# sensor_hubv3.net
KiCad netlist of a schematic drawn in EAGLE
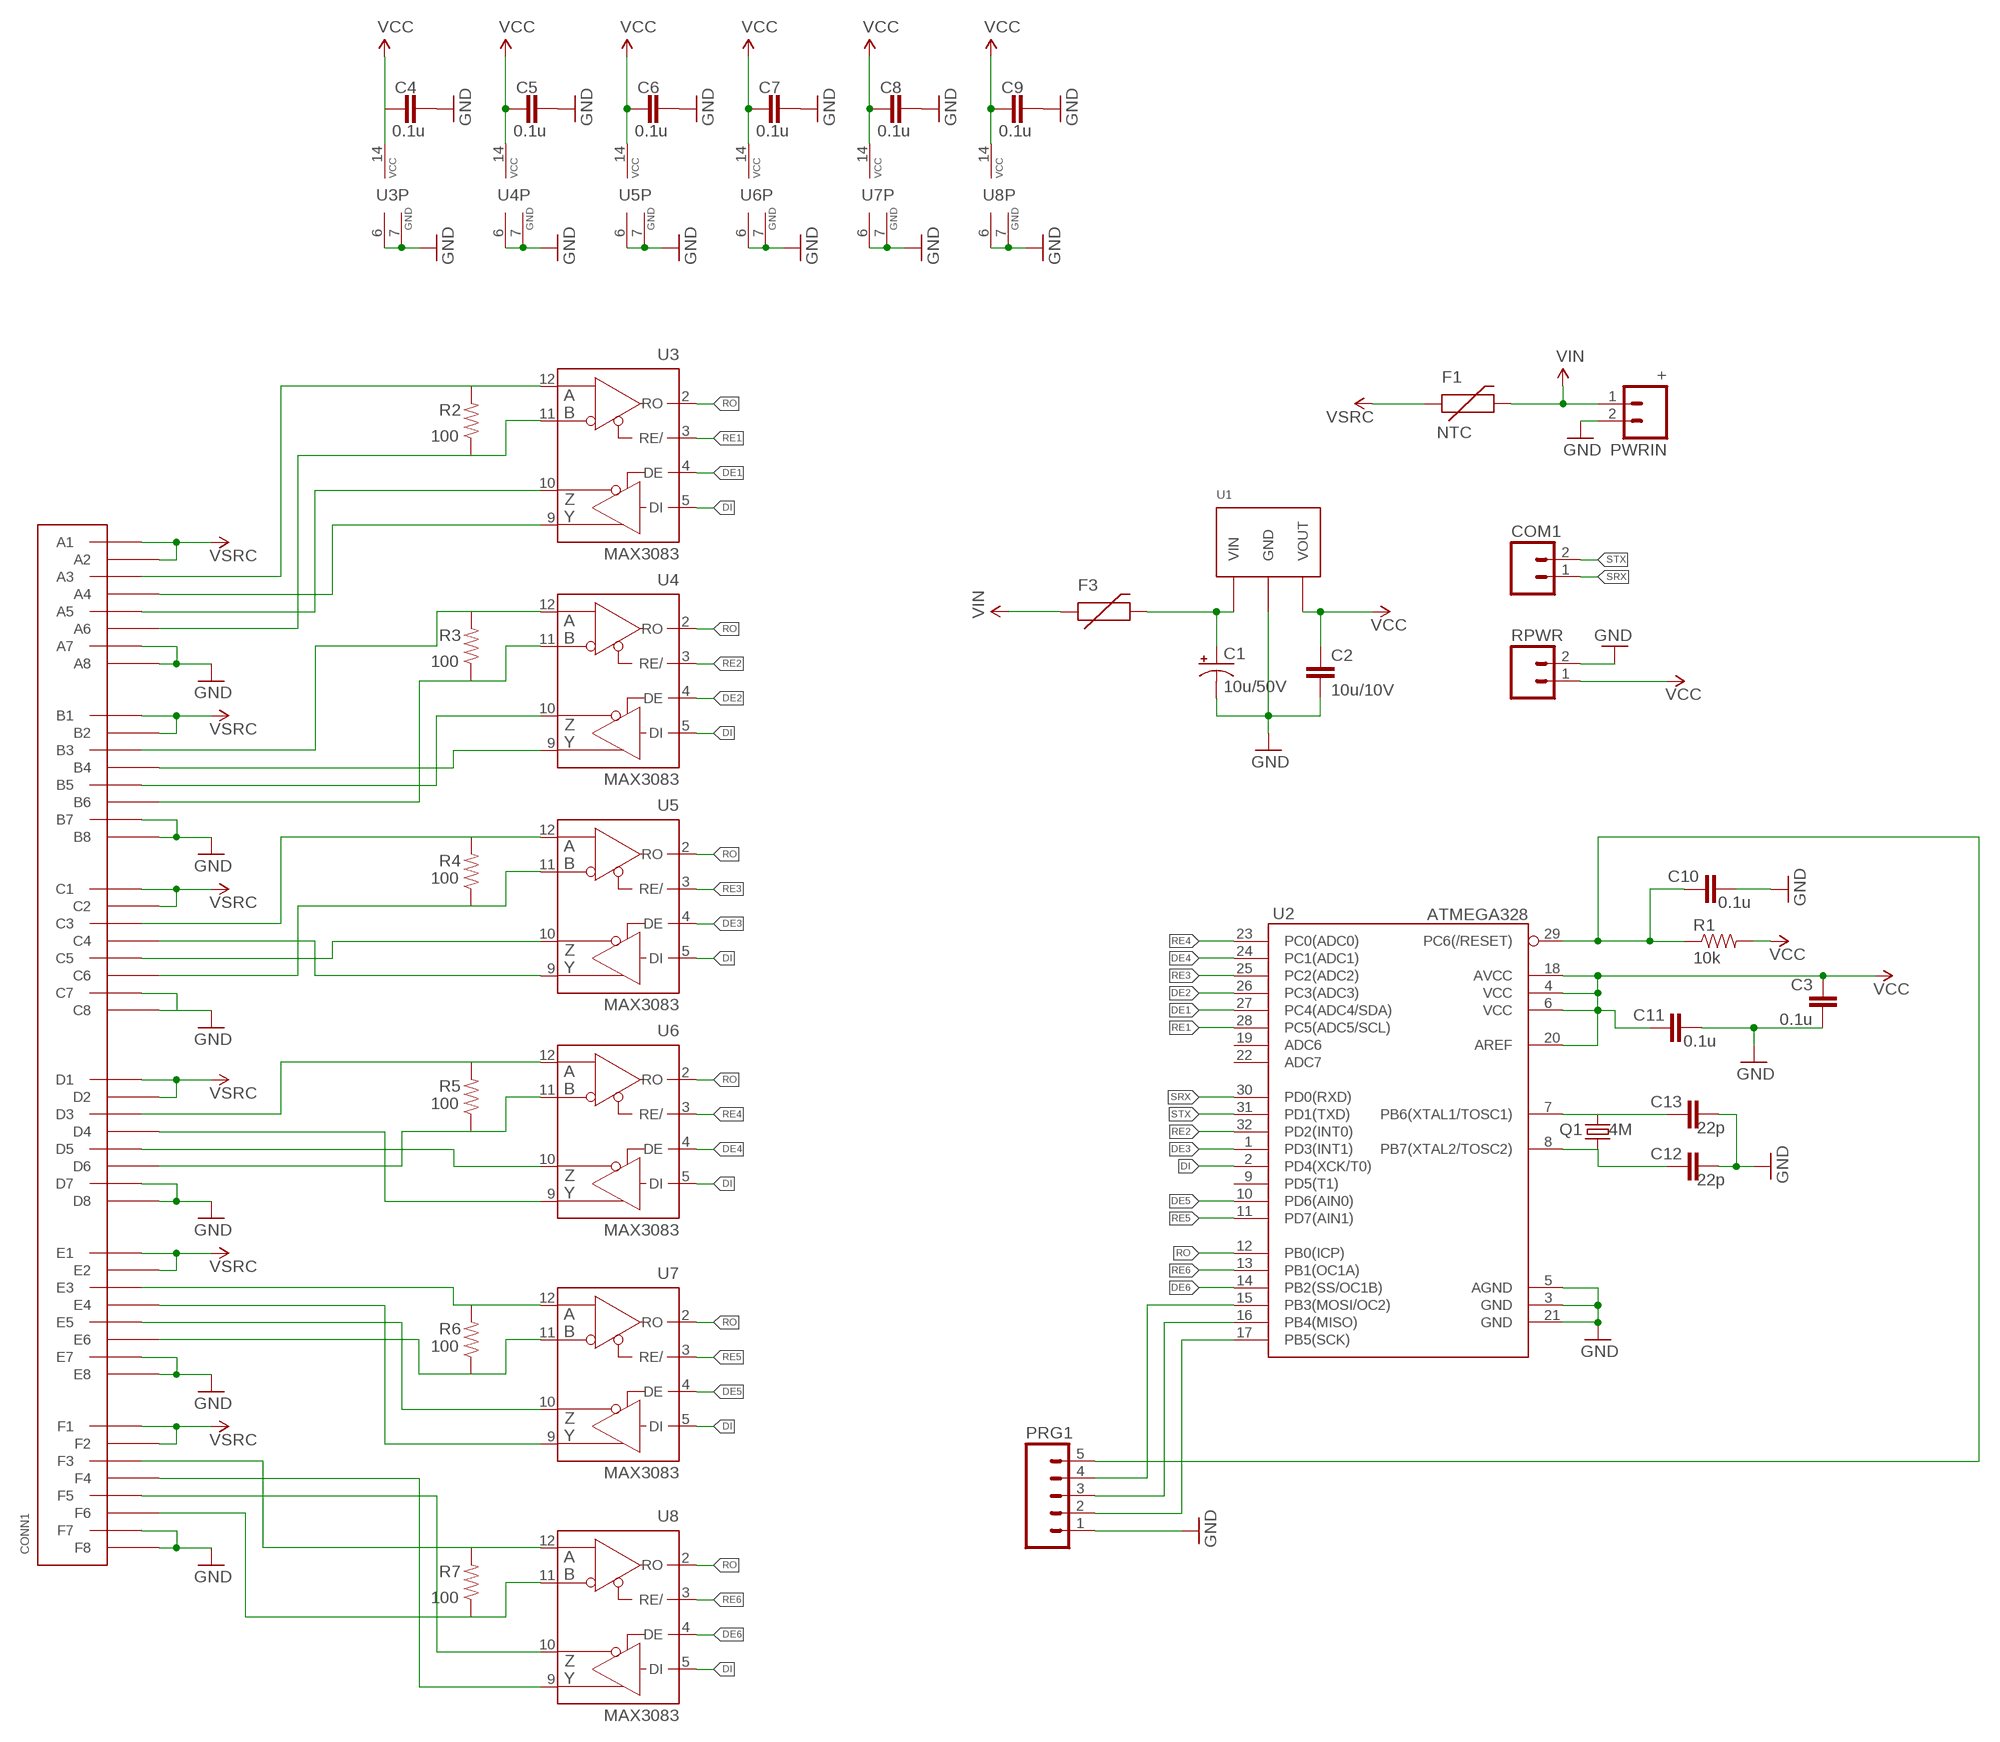
[diagram p0: schematic, sheet 1]

(export (version "E")
  (design (tool "Eeschema 10.0.6"))
  (components
    (comp (ref "C1")
      (value "10u/50V")
      (footprint "eagle-import:PANASONIC_C")
      (libsource (lib "eagle-import") (part "CAP_POLC"))
    )
    (comp (ref "C2")
      (value "10u/10V")
      (footprint "eagle-import:0805")
      (libsource (lib "eagle-import") (part "CAP0805"))
    )
    (comp (ref "C3")
      (value "0.1u")
      (footprint "eagle-import:0805")
      (libsource (lib "eagle-import") (part "CAP0805"))
    )
    (comp (ref "C4")
      (value "0.1u")
      (footprint "eagle-import:0805")
      (libsource (lib "eagle-import") (part "CAP0805"))
    )
    (comp (ref "C5")
      (value "0.1u")
      (footprint "eagle-import:0805")
      (libsource (lib "eagle-import") (part "CAP0805"))
    )
    (comp (ref "C6")
      (value "0.1u")
      (footprint "eagle-import:0805")
      (libsource (lib "eagle-import") (part "CAP0805"))
    )
    (comp (ref "C7")
      (value "0.1u")
      (footprint "eagle-import:0805")
      (libsource (lib "eagle-import") (part "CAP0805"))
    )
    (comp (ref "C8")
      (value "0.1u")
      (footprint "eagle-import:0805")
      (libsource (lib "eagle-import") (part "CAP0805"))
    )
    (comp (ref "C9")
      (value "0.1u")
      (footprint "eagle-import:0805")
      (libsource (lib "eagle-import") (part "CAP0805"))
    )
    (comp (ref "C10")
      (value "0.1u")
      (footprint "eagle-import:0805")
      (libsource (lib "eagle-import") (part "CAP0805"))
    )
    (comp (ref "C11")
      (value "0.1u")
      (footprint "eagle-import:0805")
      (libsource (lib "eagle-import") (part "CAP0805"))
    )
    (comp (ref "C12")
      (value "22p")
      (footprint "eagle-import:0805")
      (libsource (lib "eagle-import") (part "CAP0805"))
    )
    (comp (ref "C13")
      (value "22p")
      (footprint "eagle-import:0805")
      (libsource (lib "eagle-import") (part "CAP0805"))
    )
    (comp (ref "COM1")
      (value "M02LOCK_LONGPADS")
      (footprint "eagle-import:1X02_LOCK_LONGPADS")
      (libsource (lib "eagle-import") (part "M02LOCK_LONGPADS"))
    )
    (comp (ref "CONN1")
      (value "8P8C-6PORT")
      (footprint "eagle-import:4UCON-04953")
      (libsource (lib "eagle-import") (part "8P8C-6PORT"))
    )
    (comp (ref "F1")
      (value "NTC")
      (footprint "eagle-import:R-7,5")
      (libsource (lib "eagle-import") (part "PTCPTH2"))
    )
    (comp (ref "F3")
      (value "PTC0603")
      (footprint "eagle-import:0603")
      (libsource (lib "eagle-import") (part "PTC0603"))
    )
    (comp (ref "PRG1")
      (value "M05LOCK")
      (footprint "eagle-import:1X05_LOCK")
      (libsource (lib "eagle-import") (part "M05LOCK"))
    )
    (comp (ref "PWRIN")
      (value "+")
      (footprint "eagle-import:SCREWTERMINAL-5MM-2")
      (libsource (lib "eagle-import") (part "SparkFun-Connectors_M025MM"))
    )
    (comp (ref "Q1")
      (value "4M")
      (footprint "eagle-import:HC49UP")
      (libsource (lib "eagle-import") (part "CRYSTALHC49UP"))
    )
    (comp (ref "R1")
      (value "10k")
      (footprint "eagle-import:0805")
      (libsource (lib "eagle-import") (part "RESISTOR0805-RES"))
    )
    (comp (ref "R2")
      (value "100")
      (footprint "eagle-import:0805")
      (libsource (lib "eagle-import") (part "RESISTOR0805-RES"))
    )
    (comp (ref "R3")
      (value "100")
      (footprint "eagle-import:0805")
      (libsource (lib "eagle-import") (part "RESISTOR0805-RES"))
    )
    (comp (ref "R4")
      (value "100")
      (footprint "eagle-import:0805")
      (libsource (lib "eagle-import") (part "RESISTOR0805-RES"))
    )
    (comp (ref "R5")
      (value "100")
      (footprint "eagle-import:0805")
      (libsource (lib "eagle-import") (part "RESISTOR0805-RES"))
    )
    (comp (ref "R6")
      (value "100")
      (footprint "eagle-import:0805")
      (libsource (lib "eagle-import") (part "RESISTOR0805-RES"))
    )
    (comp (ref "R7")
      (value "100")
      (footprint "eagle-import:0805")
      (libsource (lib "eagle-import") (part "RESISTOR0805-RES"))
    )
    (comp (ref "RPWR")
      (value "M02LOCK_LONGPADS")
      (footprint "eagle-import:1X02_LOCK_LONGPADS")
      (libsource (lib "eagle-import") (part "M02LOCK_LONGPADS"))
    )
    (comp (ref "U1")
      (value "OKI-78SR")
      (footprint "eagle-import:OKI-78SR")
      (libsource (lib "eagle-import") (part "OKI-78SR"))
    )
    (comp (ref "U2")
      (value "ATMEGA328")
      (footprint "eagle-import:TQFP32-08")
      (libsource (lib "eagle-import") (part "ATMEGA168"))
    )
    (comp (ref "U3")
      (value "MAX3083")
      (footprint "eagle-import:SO14")
      (fields (field (name "MF") "MAXIM") (field (name "MPN") "MAX489CSD"))
      (libsource (lib "eagle-import") (part "MAX489CSD"))
    )
    (comp (ref "U4")
      (value "MAX3083")
      (footprint "eagle-import:SO14")
      (fields (field (name "MF") "MAXIM") (field (name "MPN") "MAX489CSD"))
      (libsource (lib "eagle-import") (part "MAX489CSD"))
    )
    (comp (ref "U5")
      (value "MAX3083")
      (footprint "eagle-import:SO14")
      (fields (field (name "MF") "MAXIM") (field (name "MPN") "MAX489CSD"))
      (libsource (lib "eagle-import") (part "MAX489CSD"))
    )
    (comp (ref "U6")
      (value "MAX3083")
      (footprint "eagle-import:SO14")
      (fields (field (name "MF") "MAXIM") (field (name "MPN") "MAX489CSD"))
      (libsource (lib "eagle-import") (part "MAX489CSD"))
    )
    (comp (ref "U7")
      (value "MAX3083")
      (footprint "eagle-import:SO14")
      (fields (field (name "MF") "MAXIM") (field (name "MPN") "MAX489CSD"))
      (libsource (lib "eagle-import") (part "MAX489CSD"))
    )
    (comp (ref "U8")
      (value "MAX3083")
      (footprint "eagle-import:SO14")
      (fields (field (name "MF") "MAXIM") (field (name "MPN") "MAX489CSD"))
      (libsource (lib "eagle-import") (part "MAX489CSD"))
    )
  )
  (nets
    (net (code "1") (name "DE1") (class "Default")
      (node (ref "U2") (pin "27") (pinfunction "PC4(ADC4/SDA)_27") (pintype "bidirectional"))
      (node (ref "U3") (pin "4") (pinfunction "DE_4") (pintype "input"))
    )
    (net (code "2") (name "DE2") (class "Default")
      (node (ref "U2") (pin "26") (pinfunction "PC3(ADC3)_26") (pintype "bidirectional"))
      (node (ref "U4") (pin "4") (pinfunction "DE_4") (pintype "input"))
    )
    (net (code "3") (name "DE3") (class "Default")
      (node (ref "U2") (pin "1") (pinfunction "PD3(INT1)_1") (pintype "bidirectional"))
      (node (ref "U5") (pin "4") (pinfunction "DE_4") (pintype "input"))
    )
    (net (code "4") (name "DE4") (class "Default")
      (node (ref "U2") (pin "24") (pinfunction "PC1(ADC1)_24") (pintype "bidirectional"))
      (node (ref "U6") (pin "4") (pinfunction "DE_4") (pintype "input"))
    )
    (net (code "5") (name "DE5") (class "Default")
      (node (ref "U2") (pin "10") (pinfunction "PD6(AIN0)_10") (pintype "bidirectional"))
      (node (ref "U7") (pin "4") (pinfunction "DE_4") (pintype "input"))
    )
    (net (code "6") (name "DE6") (class "Default")
      (node (ref "U2") (pin "14") (pinfunction "PB2(SS/OC1B)_14") (pintype "bidirectional"))
      (node (ref "U8") (pin "4") (pinfunction "DE_4") (pintype "input"))
    )
    (net (code "7") (name "DI") (class "Default")
      (node (ref "U2") (pin "2") (pinfunction "PD4(XCK/T0)_2") (pintype "bidirectional"))
      (node (ref "U3") (pin "5") (pinfunction "DI_5") (pintype "input"))
      (node (ref "U4") (pin "5") (pinfunction "DI_5") (pintype "input"))
      (node (ref "U5") (pin "5") (pinfunction "DI_5") (pintype "input"))
      (node (ref "U6") (pin "5") (pinfunction "DI_5") (pintype "input"))
      (node (ref "U7") (pin "5") (pinfunction "DI_5") (pintype "input"))
      (node (ref "U8") (pin "5") (pinfunction "DI_5") (pintype "input"))
    )
    (net (code "8") (name "GND") (class "Default")
      (node (ref "C1") (pin "-") (pinfunction "-_-") (pintype "passive"))
      (node (ref "C10") (pin "2") (pinfunction "2_2") (pintype "passive"))
      (node (ref "C11") (pin "2") (pinfunction "2_2") (pintype "passive"))
      (node (ref "C12") (pin "2") (pinfunction "2_2") (pintype "passive"))
      (node (ref "C13") (pin "2") (pinfunction "2_2") (pintype "passive"))
      (node (ref "C2") (pin "2") (pinfunction "2_2") (pintype "passive"))
      (node (ref "C3") (pin "1") (pinfunction "1_1") (pintype "passive"))
      (node (ref "C4") (pin "2") (pinfunction "2_2") (pintype "passive"))
      (node (ref "C5") (pin "2") (pinfunction "2_2") (pintype "passive"))
      (node (ref "C6") (pin "2") (pinfunction "2_2") (pintype "passive"))
      (node (ref "C7") (pin "2") (pinfunction "2_2") (pintype "passive"))
      (node (ref "C8") (pin "2") (pinfunction "2_2") (pintype "passive"))
      (node (ref "C9") (pin "2") (pinfunction "2_2") (pintype "passive"))
      (node (ref "CONN1") (pin "A7") (pinfunction "A7_A7") (pintype "bidirectional"))
      (node (ref "CONN1") (pin "A8") (pinfunction "A8_A8") (pintype "bidirectional"))
      (node (ref "CONN1") (pin "B7") (pinfunction "B7_B7") (pintype "bidirectional"))
      (node (ref "CONN1") (pin "B8") (pinfunction "B8_B8") (pintype "bidirectional"))
      (node (ref "CONN1") (pin "C7") (pinfunction "C7_C7") (pintype "bidirectional"))
      (node (ref "CONN1") (pin "C8") (pinfunction "C8_C8") (pintype "bidirectional"))
      (node (ref "CONN1") (pin "D7") (pinfunction "D7_D7") (pintype "bidirectional"))
      (node (ref "CONN1") (pin "D8") (pinfunction "D8_D8") (pintype "bidirectional"))
      (node (ref "CONN1") (pin "E7") (pinfunction "E7_E7") (pintype "bidirectional"))
      (node (ref "CONN1") (pin "E8") (pinfunction "E8_E8") (pintype "bidirectional"))
      (node (ref "CONN1") (pin "F7") (pinfunction "F7_F7") (pintype "bidirectional"))
      (node (ref "CONN1") (pin "F8") (pinfunction "F8_F8") (pintype "bidirectional"))
      (node (ref "PRG1") (pin "1") (pinfunction "1_1") (pintype "passive"))
      (node (ref "PWRIN") (pin "2") (pinfunction "2_2") (pintype "passive"))
      (node (ref "RPWR") (pin "2") (pinfunction "2_2") (pintype "passive"))
      (node (ref "U1") (pin "GND") (pinfunction "GND_GND") (pintype "bidirectional"))
      (node (ref "U2") (pin "21") (pinfunction "GND_21") (pintype "bidirectional"))
      (node (ref "U2") (pin "3") (pinfunction "GND_3") (pintype "bidirectional"))
      (node (ref "U2") (pin "5") (pinfunction "AGND_5") (pintype "bidirectional"))
      (node (ref "U3") (pin "6") (pinfunction "GND_6") (pintype "power_in"))
      (node (ref "U3") (pin "7") (pinfunction "GND_7") (pintype "power_in"))
      (node (ref "U4") (pin "6") (pinfunction "GND_6") (pintype "power_in"))
      (node (ref "U4") (pin "7") (pinfunction "GND_7") (pintype "power_in"))
      (node (ref "U5") (pin "6") (pinfunction "GND_6") (pintype "power_in"))
      (node (ref "U5") (pin "7") (pinfunction "GND_7") (pintype "power_in"))
      (node (ref "U6") (pin "6") (pinfunction "GND_6") (pintype "power_in"))
      (node (ref "U6") (pin "7") (pinfunction "GND_7") (pintype "power_in"))
      (node (ref "U7") (pin "6") (pinfunction "GND_6") (pintype "power_in"))
      (node (ref "U7") (pin "7") (pinfunction "GND_7") (pintype "power_in"))
      (node (ref "U8") (pin "6") (pinfunction "GND_6") (pintype "power_in"))
      (node (ref "U8") (pin "7") (pinfunction "GND_7") (pintype "power_in"))
    )
    (net (code "9") (name "Net-(C1-Pad+)") (class "Default")
      (node (ref "C1") (pin "+") (pinfunction "+_+") (pintype "passive"))
      (node (ref "F3") (pin "2") (pinfunction "2_2") (pintype "bidirectional"))
      (node (ref "U1") (pin "VIN") (pinfunction "VIN_VIN") (pintype "bidirectional"))
    )
    (net (code "10") (name "Net-(U2-PB3(MOSI{slash}OC2))") (class "Default")
      (node (ref "PRG1") (pin "4") (pinfunction "4_4") (pintype "passive"))
      (node (ref "U2") (pin "15") (pinfunction "PB3(MOSI/OC2)_15") (pintype "bidirectional"))
    )
    (net (code "11") (name "Net-(U2-PB4(MISO))") (class "Default")
      (node (ref "PRG1") (pin "3") (pinfunction "3_3") (pintype "passive"))
      (node (ref "U2") (pin "16") (pinfunction "PB4(MISO)_16") (pintype "bidirectional"))
    )
    (net (code "12") (name "Net-(U2-PB5(SCK))") (class "Default")
      (node (ref "PRG1") (pin "2") (pinfunction "2_2") (pintype "passive"))
      (node (ref "U2") (pin "17") (pinfunction "PB5(SCK)_17") (pintype "bidirectional"))
    )
    (net (code "13") (name "Net-(U2-PB6(XTAL1{slash}TOSC1))") (class "Default")
      (node (ref "C13") (pin "1") (pinfunction "1_1") (pintype "passive"))
      (node (ref "Q1") (pin "2") (pinfunction "2_2") (pintype "passive"))
      (node (ref "U2") (pin "7") (pinfunction "PB6(XTAL1/TOSC1)_7") (pintype "bidirectional"))
    )
    (net (code "14") (name "Net-(U2-PB7(XTAL2{slash}TOSC2))") (class "Default")
      (node (ref "C12") (pin "1") (pinfunction "1_1") (pintype "passive"))
      (node (ref "Q1") (pin "1") (pinfunction "1_1") (pintype "passive"))
      (node (ref "U2") (pin "8") (pinfunction "PB7(XTAL2/TOSC2)_8") (pintype "bidirectional"))
    )
    (net (code "15") (name "Net-(U2-PC6({slash}RESET))") (class "Default")
      (node (ref "C10") (pin "1") (pinfunction "1_1") (pintype "passive"))
      (node (ref "PRG1") (pin "5") (pinfunction "5_5") (pintype "passive"))
      (node (ref "R1") (pin "1") (pinfunction "1_1") (pintype "passive"))
      (node (ref "U2") (pin "29") (pinfunction "PC6(/RESET)_29") (pintype "bidirectional"))
    )
    (net (code "16") (name "Net-(U3D-A)") (class "Default")
      (node (ref "CONN1") (pin "A3") (pinfunction "A3_A3") (pintype "bidirectional"))
      (node (ref "R2") (pin "2") (pinfunction "2_2") (pintype "passive"))
      (node (ref "U3") (pin "12") (pinfunction "A_12") (pintype "passive"))
    )
    (net (code "17") (name "Net-(U3D-B)") (class "Default")
      (node (ref "CONN1") (pin "A6") (pinfunction "A6_A6") (pintype "bidirectional"))
      (node (ref "R2") (pin "1") (pinfunction "1_1") (pintype "passive"))
      (node (ref "U3") (pin "11") (pinfunction "B_11") (pintype "passive"))
    )
    (net (code "18") (name "Net-(U3D-Y)") (class "Default")
      (node (ref "CONN1") (pin "A4") (pinfunction "A4_A4") (pintype "bidirectional"))
      (node (ref "U3") (pin "9") (pinfunction "Y_9") (pintype "passive"))
    )
    (net (code "19") (name "Net-(U3D-Z)") (class "Default")
      (node (ref "CONN1") (pin "A5") (pinfunction "A5_A5") (pintype "bidirectional"))
      (node (ref "U3") (pin "10") (pinfunction "Z_10") (pintype "passive"))
    )
    (net (code "20") (name "Net-(U4D-A)") (class "Default")
      (node (ref "CONN1") (pin "B3") (pinfunction "B3_B3") (pintype "bidirectional"))
      (node (ref "R3") (pin "2") (pinfunction "2_2") (pintype "passive"))
      (node (ref "U4") (pin "12") (pinfunction "A_12") (pintype "passive"))
    )
    (net (code "21") (name "Net-(U4D-B)") (class "Default")
      (node (ref "CONN1") (pin "B6") (pinfunction "B6_B6") (pintype "bidirectional"))
      (node (ref "R3") (pin "1") (pinfunction "1_1") (pintype "passive"))
      (node (ref "U4") (pin "11") (pinfunction "B_11") (pintype "passive"))
    )
    (net (code "22") (name "Net-(U4D-Y)") (class "Default")
      (node (ref "CONN1") (pin "B4") (pinfunction "B4_B4") (pintype "bidirectional"))
      (node (ref "U4") (pin "9") (pinfunction "Y_9") (pintype "passive"))
    )
    (net (code "23") (name "Net-(U4D-Z)") (class "Default")
      (node (ref "CONN1") (pin "B5") (pinfunction "B5_B5") (pintype "bidirectional"))
      (node (ref "U4") (pin "10") (pinfunction "Z_10") (pintype "passive"))
    )
    (net (code "24") (name "Net-(U5D-A)") (class "Default")
      (node (ref "CONN1") (pin "C3") (pinfunction "C3_C3") (pintype "bidirectional"))
      (node (ref "R4") (pin "2") (pinfunction "2_2") (pintype "passive"))
      (node (ref "U5") (pin "12") (pinfunction "A_12") (pintype "passive"))
    )
    (net (code "25") (name "Net-(U5D-B)") (class "Default")
      (node (ref "CONN1") (pin "C6") (pinfunction "C6_C6") (pintype "bidirectional"))
      (node (ref "R4") (pin "1") (pinfunction "1_1") (pintype "passive"))
      (node (ref "U5") (pin "11") (pinfunction "B_11") (pintype "passive"))
    )
    (net (code "26") (name "Net-(U5D-Y)") (class "Default")
      (node (ref "CONN1") (pin "C4") (pinfunction "C4_C4") (pintype "bidirectional"))
      (node (ref "U5") (pin "9") (pinfunction "Y_9") (pintype "passive"))
    )
    (net (code "27") (name "Net-(U5D-Z)") (class "Default")
      (node (ref "CONN1") (pin "C5") (pinfunction "C5_C5") (pintype "bidirectional"))
      (node (ref "U5") (pin "10") (pinfunction "Z_10") (pintype "passive"))
    )
    (net (code "28") (name "Net-(U6D-A)") (class "Default")
      (node (ref "CONN1") (pin "D3") (pinfunction "D3_D3") (pintype "bidirectional"))
      (node (ref "R5") (pin "2") (pinfunction "2_2") (pintype "passive"))
      (node (ref "U6") (pin "12") (pinfunction "A_12") (pintype "passive"))
    )
    (net (code "29") (name "Net-(U6D-B)") (class "Default")
      (node (ref "CONN1") (pin "D6") (pinfunction "D6_D6") (pintype "bidirectional"))
      (node (ref "R5") (pin "1") (pinfunction "1_1") (pintype "passive"))
      (node (ref "U6") (pin "11") (pinfunction "B_11") (pintype "passive"))
    )
    (net (code "30") (name "Net-(U6D-Y)") (class "Default")
      (node (ref "CONN1") (pin "D4") (pinfunction "D4_D4") (pintype "bidirectional"))
      (node (ref "U6") (pin "9") (pinfunction "Y_9") (pintype "passive"))
    )
    (net (code "31") (name "Net-(U6D-Z)") (class "Default")
      (node (ref "CONN1") (pin "D5") (pinfunction "D5_D5") (pintype "bidirectional"))
      (node (ref "U6") (pin "10") (pinfunction "Z_10") (pintype "passive"))
    )
    (net (code "32") (name "Net-(U7D-A)") (class "Default")
      (node (ref "CONN1") (pin "E3") (pinfunction "E3_E3") (pintype "bidirectional"))
      (node (ref "R6") (pin "2") (pinfunction "2_2") (pintype "passive"))
      (node (ref "U7") (pin "12") (pinfunction "A_12") (pintype "passive"))
    )
    (net (code "33") (name "Net-(U7D-B)") (class "Default")
      (node (ref "CONN1") (pin "E6") (pinfunction "E6_E6") (pintype "bidirectional"))
      (node (ref "R6") (pin "1") (pinfunction "1_1") (pintype "passive"))
      (node (ref "U7") (pin "11") (pinfunction "B_11") (pintype "passive"))
    )
    (net (code "34") (name "Net-(U7D-Y)") (class "Default")
      (node (ref "CONN1") (pin "E4") (pinfunction "E4_E4") (pintype "bidirectional"))
      (node (ref "U7") (pin "9") (pinfunction "Y_9") (pintype "passive"))
    )
    (net (code "35") (name "Net-(U7D-Z)") (class "Default")
      (node (ref "CONN1") (pin "E5") (pinfunction "E5_E5") (pintype "bidirectional"))
      (node (ref "U7") (pin "10") (pinfunction "Z_10") (pintype "passive"))
    )
    (net (code "36") (name "Net-(U8D-A)") (class "Default")
      (node (ref "CONN1") (pin "F3") (pinfunction "F3_F3") (pintype "bidirectional"))
      (node (ref "R7") (pin "2") (pinfunction "2_2") (pintype "passive"))
      (node (ref "U8") (pin "12") (pinfunction "A_12") (pintype "passive"))
    )
    (net (code "37") (name "Net-(U8D-B)") (class "Default")
      (node (ref "CONN1") (pin "F6") (pinfunction "F6_F6") (pintype "bidirectional"))
      (node (ref "R7") (pin "1") (pinfunction "1_1") (pintype "passive"))
      (node (ref "U8") (pin "11") (pinfunction "B_11") (pintype "passive"))
    )
    (net (code "38") (name "Net-(U8D-Y)") (class "Default")
      (node (ref "CONN1") (pin "F4") (pinfunction "F4_F4") (pintype "bidirectional"))
      (node (ref "U8") (pin "9") (pinfunction "Y_9") (pintype "passive"))
    )
    (net (code "39") (name "Net-(U8D-Z)") (class "Default")
      (node (ref "CONN1") (pin "F5") (pinfunction "F5_F5") (pintype "bidirectional"))
      (node (ref "U8") (pin "10") (pinfunction "Z_10") (pintype "passive"))
    )
    (net (code "40") (name "RE1") (class "Default")
      (node (ref "U2") (pin "28") (pinfunction "PC5(ADC5/SCL)_28") (pintype "bidirectional"))
      (node (ref "U3") (pin "3") (pinfunction "RE/_3") (pintype "input"))
    )
    (net (code "41") (name "RE2") (class "Default")
      (node (ref "U2") (pin "32") (pinfunction "PD2(INT0)_32") (pintype "bidirectional"))
      (node (ref "U4") (pin "3") (pinfunction "RE/_3") (pintype "input"))
    )
    (net (code "42") (name "RE3") (class "Default")
      (node (ref "U2") (pin "25") (pinfunction "PC2(ADC2)_25") (pintype "bidirectional"))
      (node (ref "U5") (pin "3") (pinfunction "RE/_3") (pintype "input"))
    )
    (net (code "43") (name "RE4") (class "Default")
      (node (ref "U2") (pin "23") (pinfunction "PC0(ADC0)_23") (pintype "bidirectional"))
      (node (ref "U6") (pin "3") (pinfunction "RE/_3") (pintype "input"))
    )
    (net (code "44") (name "RE5") (class "Default")
      (node (ref "U2") (pin "11") (pinfunction "PD7(AIN1)_11") (pintype "bidirectional"))
      (node (ref "U7") (pin "3") (pinfunction "RE/_3") (pintype "input"))
    )
    (net (code "45") (name "RE6") (class "Default")
      (node (ref "U2") (pin "13") (pinfunction "PB1(OC1A)_13") (pintype "bidirectional"))
      (node (ref "U8") (pin "3") (pinfunction "RE/_3") (pintype "input"))
    )
    (net (code "46") (name "RO") (class "Default")
      (node (ref "U2") (pin "12") (pinfunction "PB0(ICP)_12") (pintype "bidirectional"))
      (node (ref "U3") (pin "2") (pinfunction "RO_2") (pintype "output"))
      (node (ref "U4") (pin "2") (pinfunction "RO_2") (pintype "output"))
      (node (ref "U5") (pin "2") (pinfunction "RO_2") (pintype "output"))
      (node (ref "U6") (pin "2") (pinfunction "RO_2") (pintype "output"))
      (node (ref "U7") (pin "2") (pinfunction "RO_2") (pintype "output"))
      (node (ref "U8") (pin "2") (pinfunction "RO_2") (pintype "output"))
    )
    (net (code "47") (name "SRX") (class "Default")
      (node (ref "COM1") (pin "1") (pinfunction "1_1") (pintype "passive"))
      (node (ref "U2") (pin "30") (pinfunction "PD0(RXD)_30") (pintype "bidirectional"))
    )
    (net (code "48") (name "STX") (class "Default")
      (node (ref "COM1") (pin "2") (pinfunction "2_2") (pintype "passive"))
      (node (ref "U2") (pin "31") (pinfunction "PD1(TXD)_31") (pintype "bidirectional"))
    )
    (net (code "49") (name "VCC") (class "Default")
      (node (ref "C11") (pin "1") (pinfunction "1_1") (pintype "passive"))
      (node (ref "C2") (pin "1") (pinfunction "1_1") (pintype "passive"))
      (node (ref "C3") (pin "2") (pinfunction "2_2") (pintype "passive"))
      (node (ref "C4") (pin "1") (pinfunction "1_1") (pintype "passive"))
      (node (ref "C5") (pin "1") (pinfunction "1_1") (pintype "passive"))
      (node (ref "C6") (pin "1") (pinfunction "1_1") (pintype "passive"))
      (node (ref "C7") (pin "1") (pinfunction "1_1") (pintype "passive"))
      (node (ref "C8") (pin "1") (pinfunction "1_1") (pintype "passive"))
      (node (ref "C9") (pin "1") (pinfunction "1_1") (pintype "passive"))
      (node (ref "R1") (pin "2") (pinfunction "2_2") (pintype "passive"))
      (node (ref "RPWR") (pin "1") (pinfunction "1_1") (pintype "passive"))
      (node (ref "U1") (pin "VOUT") (pinfunction "VOUT_VOUT") (pintype "bidirectional"))
      (node (ref "U2") (pin "18") (pinfunction "AVCC_18") (pintype "bidirectional"))
      (node (ref "U2") (pin "20") (pinfunction "AREF_20") (pintype "bidirectional"))
      (node (ref "U2") (pin "4") (pinfunction "VCC_4") (pintype "bidirectional"))
      (node (ref "U2") (pin "6") (pinfunction "VCC_6") (pintype "bidirectional"))
      (node (ref "U3") (pin "14") (pinfunction "VCC_14") (pintype "power_in"))
      (node (ref "U4") (pin "14") (pinfunction "VCC_14") (pintype "power_in"))
      (node (ref "U5") (pin "14") (pinfunction "VCC_14") (pintype "power_in"))
      (node (ref "U6") (pin "14") (pinfunction "VCC_14") (pintype "power_in"))
      (node (ref "U7") (pin "14") (pinfunction "VCC_14") (pintype "power_in"))
      (node (ref "U8") (pin "14") (pinfunction "VCC_14") (pintype "power_in"))
    )
    (net (code "50") (name "VIN") (class "Default")
      (node (ref "F1") (pin "P$2") (pinfunction "2_P$2") (pintype "bidirectional"))
      (node (ref "F3") (pin "1") (pinfunction "1_1") (pintype "bidirectional"))
      (node (ref "PWRIN") (pin "1") (pinfunction "1_1") (pintype "passive"))
    )
    (net (code "51") (name "VSRC") (class "Default")
      (node (ref "CONN1") (pin "A1") (pinfunction "A1_A1") (pintype "bidirectional"))
      (node (ref "CONN1") (pin "A2") (pinfunction "A2_A2") (pintype "bidirectional"))
      (node (ref "CONN1") (pin "B1") (pinfunction "B1_B1") (pintype "bidirectional"))
      (node (ref "CONN1") (pin "B2") (pinfunction "B2_B2") (pintype "bidirectional"))
      (node (ref "CONN1") (pin "C1") (pinfunction "C1_C1") (pintype "bidirectional"))
      (node (ref "CONN1") (pin "C2") (pinfunction "C2_C2") (pintype "bidirectional"))
      (node (ref "CONN1") (pin "D1") (pinfunction "D1_D1") (pintype "bidirectional"))
      (node (ref "CONN1") (pin "D2") (pinfunction "D2_D2") (pintype "bidirectional"))
      (node (ref "CONN1") (pin "E1") (pinfunction "E1_E1") (pintype "bidirectional"))
      (node (ref "CONN1") (pin "E2") (pinfunction "E2_E2") (pintype "bidirectional"))
      (node (ref "CONN1") (pin "F1") (pinfunction "F1_F1") (pintype "bidirectional"))
      (node (ref "CONN1") (pin "F2") (pinfunction "F2_F2") (pintype "bidirectional"))
      (node (ref "F1") (pin "P$1") (pinfunction "1_P$1") (pintype "bidirectional"))
    )
    (net (code "52") (name "unconnected-(U2-ADC6-Pad19)") (class "Default")
      (node (ref "U2") (pin "19") (pinfunction "ADC6_19") (pintype "bidirectional"))
    )
    (net (code "53") (name "unconnected-(U2-ADC7-Pad22)") (class "Default")
      (node (ref "U2") (pin "22") (pinfunction "ADC7_22") (pintype "bidirectional"))
    )
    (net (code "54") (name "unconnected-(U2-PD5(T1)-Pad9)") (class "Default")
      (node (ref "U2") (pin "9") (pinfunction "PD5(T1)_9") (pintype "bidirectional"))
    )
  )
)
